# Display.net
KiCad netlist of a schematic drawn in Altium Designer
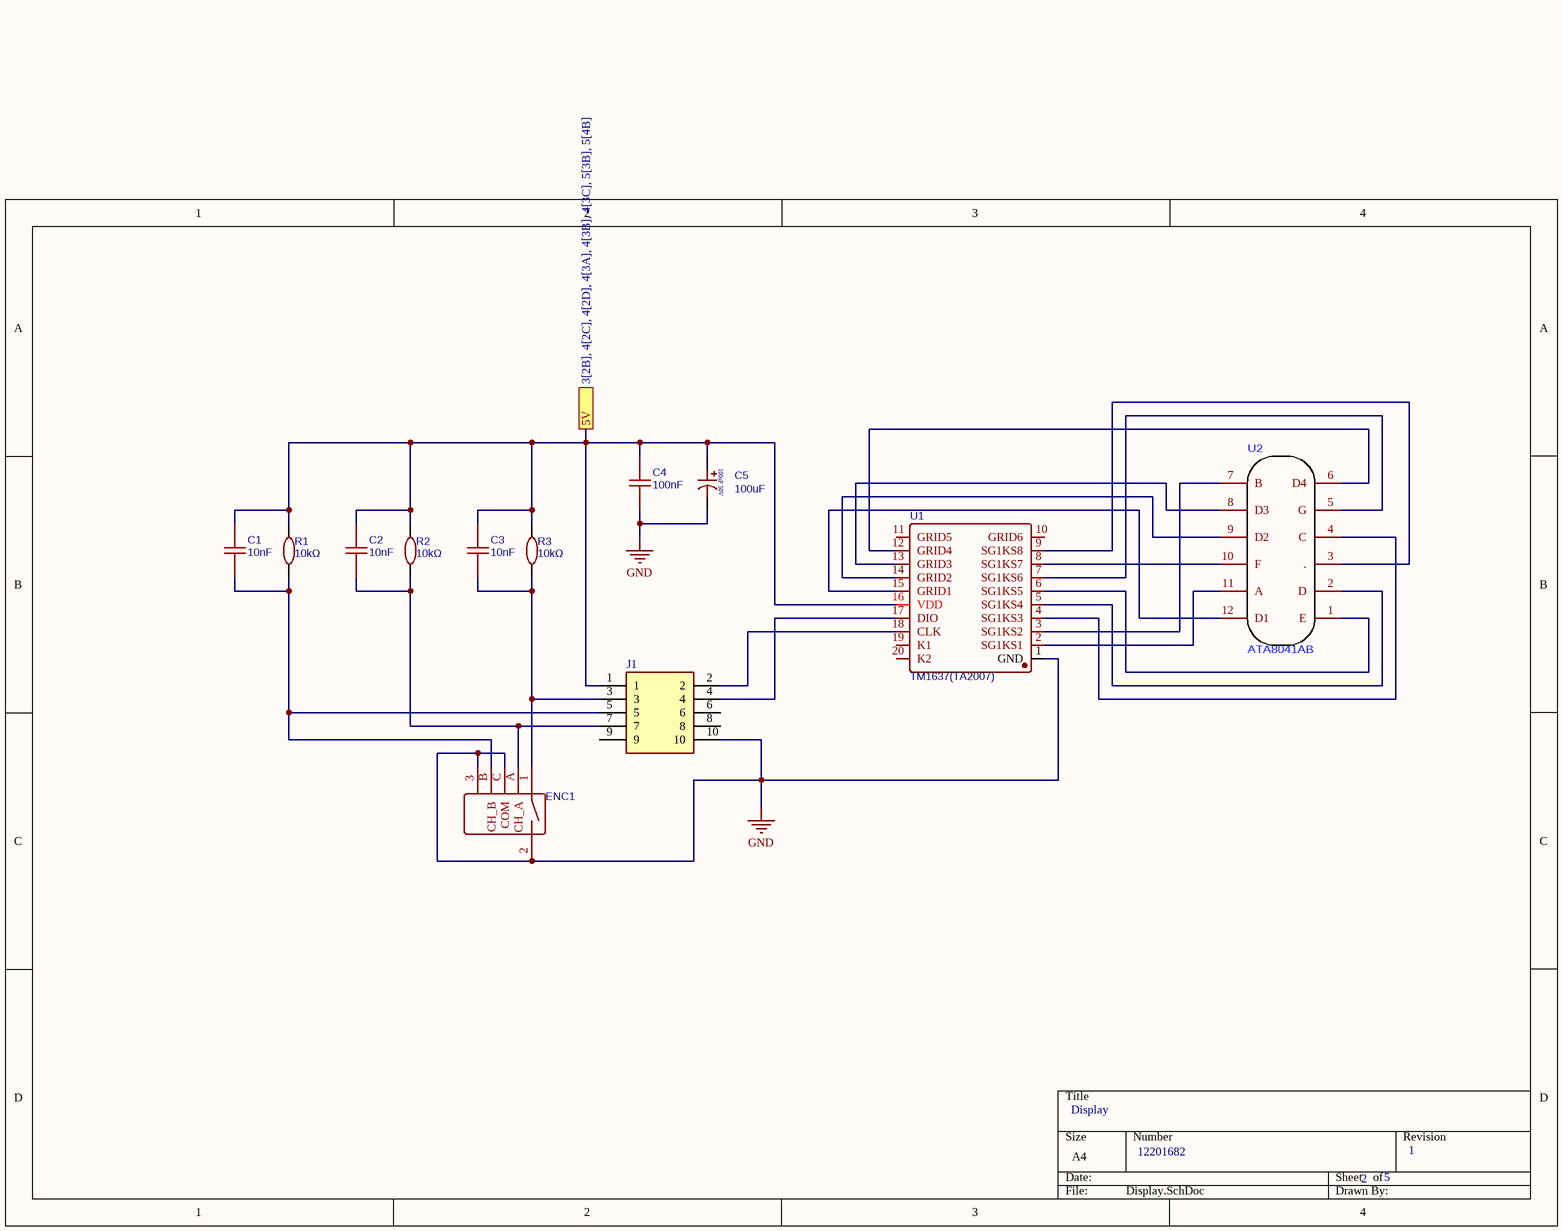
[diagram p0: Display.SchDoc]

(export (version "E")
  (design (tool "Eeschema 10.0.6"))
  (components
    (comp (ref "C1")
      (value "10nF")
      (footprint "10nF")
      (fields
        (field (name "BOM_SUPPLIER PART") "C376921")
        (field (name "BOM_MANUFACTURER PART") "TCC0805X7R103M500DT")
        (field (name "CONTRIBUTOR") "LCSC")
      )
      (libsource (lib "Soldering_Station_Library") (part "10nF"))
    )
    (comp (ref "C2")
      (value "10nF")
      (footprint "10nf")
      (fields
        (field (name "BOM_SUPPLIER PART") "C376921")
        (field (name "BOM_MANUFACTURER PART") "TCC0805X7R103M500DT")
        (field (name "CONTRIBUTOR") "LCSC")
      )
      (libsource (lib "Soldering_Station_Library") (part "10nF"))
    )
    (comp (ref "C3")
      (value "10nF")
      (footprint "10nf")
      (fields
        (field (name "BOM_SUPPLIER PART") "C376921")
        (field (name "BOM_MANUFACTURER PART") "TCC0805X7R103M500DT")
        (field (name "CONTRIBUTOR") "LCSC")
      )
      (libsource (lib "Soldering_Station_Library") (part "10nF"))
    )
    (comp (ref "C4")
      (value "100nF")
      (footprint "10nf")
      (fields
        (field (name "BOM_SUPPLIER PART") "C376921")
        (field (name "BOM_MANUFACTURER PART") "TCC0805X7R103M500DT")
        (field (name "CONTRIBUTOR") "LCSC")
      )
      (libsource (lib "Soldering_Station_Library") (part "10nF"))
    )
    (comp (ref "C5")
      (value "100uF")
      (footprint "100uF 50V")
      (fields
        (field (name "BOM_SUPPLIER PART") "C445063")
        (field (name "BOM_MANUFACTURER PART") "UWT1H101MNL1GS")
        (field (name "CONTRIBUTOR") "LCSC")
      )
      (libsource (lib "Soldering_Station_Library") (part "100uF_50V"))
    )
    (comp (ref "ENC1")
      (value "PEC11R-4220F-S0012")
      (footprint "PEC11R-4220F-S0012")
      (fields (field (name "BOM_SUPPLIER PART") "C143817") (field (name "CONTRIBUTOR") "LCSC"))
      (libsource (lib "Soldering_Station_Library") (part "PEC11R-4220F-S0012"))
    )
    (comp (ref "J1")
      (value "5104338-1")
      (footprint "10 Pin Boxheader")
      (description "Header vert 10 way 2.54mm AmpLatch")
      (fields (field (name "MOUSER PART NUMBER") "571-5104338-1"))
      (libsource (lib "Soldering_Station_Library") (part "10 Pin Boxheader"))
    )
    (comp (ref "R1")
      (value "10kΩ")
      (footprint "R0805")
      (fields
        (field (name "BOM_MANUFACTURER PART") "0805W8F1002T5E")
        (field (name "BOM_SUPPLIER PART") "C17414")
      )
      (libsource (lib "Soldering_Station_Library") (part "10kΩ"))
    )
    (comp (ref "R2")
      (value "10kΩ")
      (footprint "R0805")
      (fields
        (field (name "BOM_MANUFACTURER PART") "0805W8F1002T5E")
        (field (name "BOM_SUPPLIER PART") "C17414")
      )
      (libsource (lib "Soldering_Station_Library") (part "10kΩ"))
    )
    (comp (ref "R3")
      (value "10kΩ")
      (footprint "R0805")
      (fields
        (field (name "BOM_MANUFACTURER PART") "0805W8F1002T5E")
        (field (name "BOM_SUPPLIER PART") "C17414")
      )
      (libsource (lib "Soldering_Station_Library") (part "10kΩ"))
    )
    (comp (ref "U1")
      (value "TM1637(TA2007)")
      (footprint "TM1637(TA2007)")
      (fields (field (name "BOM_SUPPLIER PART") "C5337160") (field (name "CONTRIBUTOR") "lcsc"))
      (libsource (lib "Soldering_Station_Library") (part "TM1637(TA2007)"))
    )
    (comp (ref "U2")
      (value "ATA8041AB")
      (footprint "ATA8041AB FOOTPRINT")
      (libsource (lib "Soldering_Station_Library") (part "ATA8041AB"))
    )
  )
  (nets
    (net (code "1") (name "/5V") (class "Default")
      (node (ref "C1") (pin "2") (pinfunction "2_2") (pintype "passive"))
      (node (ref "C2") (pin "2") (pinfunction "2_2") (pintype "passive"))
      (node (ref "C3") (pin "2") (pinfunction "2_2") (pintype "passive"))
      (node (ref "C4") (pin "2") (pinfunction "2_2") (pintype "passive"))
      (node (ref "C5") (pin "1") (pinfunction "1_1") (pintype "passive"))
      (node (ref "J1") (pin "1") (pinfunction "1_1") (pintype "passive"))
      (node (ref "R1") (pin "2") (pinfunction "2_2") (pintype "passive"))
      (node (ref "R2") (pin "2") (pinfunction "2_2") (pintype "passive"))
      (node (ref "R3") (pin "2") (pinfunction "2_2") (pintype "passive"))
      (node (ref "U1") (pin "16") (pinfunction "VDD_16") (pintype "passive"))
    )
    (net (code "2") (name "GND") (class "Default")
      (node (ref "C4") (pin "1") (pinfunction "1_1") (pintype "passive"))
      (node (ref "C5") (pin "2") (pinfunction "2_2") (pintype "passive"))
      (node (ref "ENC1") (pin "2") (pintype "passive"))
      (node (ref "ENC1") (pin "3") (pintype "passive"))
      (node (ref "ENC1") (pin "C") (pinfunction "COM_C") (pintype "passive"))
      (node (ref "J1") (pin "10") (pinfunction "10_10") (pintype "passive"))
      (node (ref "U1") (pin "1") (pinfunction "GND_1") (pintype "passive"))
    )
    (net (code "3") (name "Net-(C3-Pad1)") (class "Default")
      (node (ref "C3") (pin "1") (pinfunction "1_1") (pintype "passive"))
      (node (ref "ENC1") (pin "1") (pintype "passive"))
      (node (ref "J1") (pin "3") (pinfunction "3_3") (pintype "passive"))
      (node (ref "R3") (pin "1") (pinfunction "1_1") (pintype "passive"))
    )
    (net (code "4") (name "Net-(ENC1-CH_A)") (class "Default")
      (node (ref "C2") (pin "1") (pinfunction "1_1") (pintype "passive"))
      (node (ref "ENC1") (pin "A") (pinfunction "CH_A_A") (pintype "passive"))
      (node (ref "J1") (pin "7") (pinfunction "7_7") (pintype "passive"))
      (node (ref "R2") (pin "1") (pinfunction "1_1") (pintype "passive"))
    )
    (net (code "5") (name "Net-(ENC1-CH_B)") (class "Default")
      (node (ref "C1") (pin "1") (pinfunction "1_1") (pintype "passive"))
      (node (ref "ENC1") (pin "B") (pinfunction "CH_B_B") (pintype "passive"))
      (node (ref "J1") (pin "5") (pinfunction "5_5") (pintype "passive"))
      (node (ref "R1") (pin "1") (pinfunction "1_1") (pintype "passive"))
    )
    (net (code "6") (name "Net-(U1-CLK)") (class "Default")
      (node (ref "J1") (pin "2") (pinfunction "2_2") (pintype "passive"))
      (node (ref "U1") (pin "18") (pinfunction "CLK_18") (pintype "passive"))
    )
    (net (code "7") (name "Net-(U1-DIO)") (class "Default")
      (node (ref "J1") (pin "4") (pinfunction "4_4") (pintype "passive"))
      (node (ref "U1") (pin "17") (pinfunction "DIO_17") (pintype "passive"))
    )
    (net (code "8") (name "Net-(U1-GRID1)") (class "Default")
      (node (ref "U1") (pin "15") (pinfunction "GRID1_15") (pintype "passive"))
      (node (ref "U2") (pin "12") (pinfunction "D1_12") (pintype "passive"))
    )
    (net (code "9") (name "Net-(U1-GRID2)") (class "Default")
      (node (ref "U1") (pin "14") (pinfunction "GRID2_14") (pintype "passive"))
      (node (ref "U2") (pin "9") (pinfunction "D2_9") (pintype "passive"))
    )
    (net (code "10") (name "Net-(U1-GRID3)") (class "Default")
      (node (ref "U1") (pin "13") (pinfunction "GRID3_13") (pintype "passive"))
      (node (ref "U2") (pin "8") (pinfunction "D3_8") (pintype "passive"))
    )
    (net (code "11") (name "Net-(U1-GRID4)") (class "Default")
      (node (ref "U1") (pin "12") (pinfunction "GRID4_12") (pintype "passive"))
      (node (ref "U2") (pin "6") (pinfunction "D4_6") (pintype "passive"))
    )
    (net (code "12") (name "Net-(U1-SG1KS1)") (class "Default")
      (node (ref "U1") (pin "2") (pinfunction "SG1KS1_2") (pintype "passive"))
      (node (ref "U2") (pin "11") (pinfunction "A_11") (pintype "passive"))
    )
    (net (code "13") (name "Net-(U1-SG1KS2)") (class "Default")
      (node (ref "U1") (pin "3") (pinfunction "SG1KS2_3") (pintype "passive"))
      (node (ref "U2") (pin "7") (pinfunction "B_7") (pintype "passive"))
    )
    (net (code "14") (name "Net-(U1-SG1KS3)") (class "Default")
      (node (ref "U1") (pin "4") (pinfunction "SG1KS3_4") (pintype "passive"))
      (node (ref "U2") (pin "4") (pinfunction "C_4") (pintype "passive"))
    )
    (net (code "15") (name "Net-(U1-SG1KS4)") (class "Default")
      (node (ref "U1") (pin "5") (pinfunction "SG1KS4_5") (pintype "passive"))
      (node (ref "U2") (pin "2") (pinfunction "D_2") (pintype "passive"))
    )
    (net (code "16") (name "Net-(U1-SG1KS5)") (class "Default")
      (node (ref "U1") (pin "6") (pinfunction "SG1KS5_6") (pintype "passive"))
      (node (ref "U2") (pin "1") (pinfunction "E_1") (pintype "passive"))
    )
    (net (code "17") (name "Net-(U1-SG1KS6)") (class "Default")
      (node (ref "U1") (pin "7") (pinfunction "SG1KS6_7") (pintype "passive"))
      (node (ref "U2") (pin "5") (pinfunction "G_5") (pintype "passive"))
    )
    (net (code "18") (name "Net-(U1-SG1KS7)") (class "Default")
      (node (ref "U1") (pin "8") (pinfunction "SG1KS7_8") (pintype "passive"))
      (node (ref "U2") (pin "10") (pinfunction "F_10") (pintype "passive"))
    )
    (net (code "19") (name "Net-(U1-SG1KS8)") (class "Default")
      (node (ref "U1") (pin "9") (pinfunction "SG1KS8_9") (pintype "passive"))
      (node (ref "U2") (pin "3") (pinfunction "._3") (pintype "passive"))
    )
    (net (code "20") (name "unconnected-(J1-Pad6)") (class "Default")
      (node (ref "J1") (pin "6") (pinfunction "6_6") (pintype "passive"))
    )
    (net (code "21") (name "unconnected-(J1-Pad8)") (class "Default")
      (node (ref "J1") (pin "8") (pinfunction "8_8") (pintype "passive"))
    )
    (net (code "22") (name "unconnected-(J1-Pad9)") (class "Default")
      (node (ref "J1") (pin "9") (pinfunction "9_9") (pintype "passive"))
    )
    (net (code "23") (name "unconnected-(U1-GRID5-Pad11)") (class "Default")
      (node (ref "U1") (pin "11") (pinfunction "GRID5_11") (pintype "passive"))
    )
    (net (code "24") (name "unconnected-(U1-GRID6-Pad10)") (class "Default")
      (node (ref "U1") (pin "10") (pinfunction "GRID6_10") (pintype "passive"))
    )
    (net (code "25") (name "unconnected-(U1-K1-Pad19)") (class "Default")
      (node (ref "U1") (pin "19") (pinfunction "K1_19") (pintype "passive"))
    )
    (net (code "26") (name "unconnected-(U1-K2-Pad20)") (class "Default")
      (node (ref "U1") (pin "20") (pinfunction "K2_20") (pintype "passive"))
    )
  )
)
